# mcu.net
KiCad netlist of a schematic drawn in Altium Designer
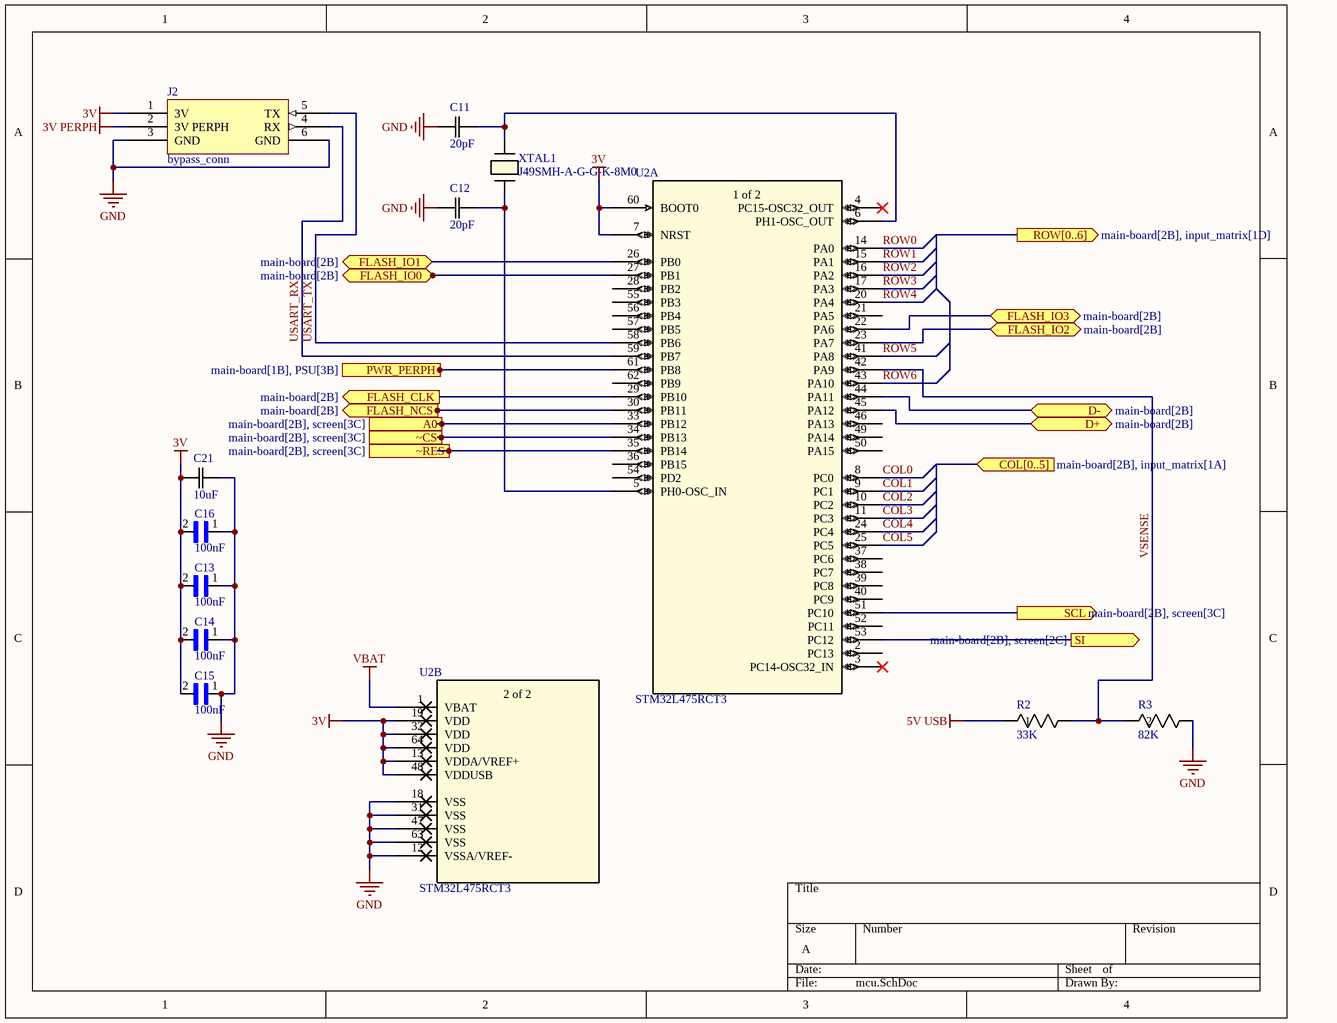
[diagram p0: mcu.SchDoc]

(export (version "E")
  (design (tool "Eeschema 10.0.6"))
  (components
    (comp (ref "C11")
      (value "20pF")
      (footprint "CAP_CL10_SAM")
      (description "CL10C200JB8NNNC")
      (libsource (lib "CL10C200JB8NNNC") (part "CL10C200JB8NNNC"))
    )
    (comp (ref "C12")
      (value "20pF")
      (footprint "CAP_CL10_SAM")
      (description "CL10C200JB8NNNC")
      (libsource (lib "CL10C200JB8NNNC") (part "CL10C200JB8NNNC"))
    )
    (comp (ref "C13")
      (value "100nF")
      (footprint "CAPC1005X55N")
      (description "0.1ÂµF Â±10% 10V Ceramic Capacitor X7R 0402 _1005 Metric_")
      (fields (field (name "MP") "CL05B104KP5NNNC") (field (name "MF") "Samsung Electro-Mechanics"))
      (libsource (lib "CL05B104KP5NNNC") (part "CL05B104KP5NNNC"))
    )
    (comp (ref "C14")
      (value "100nF")
      (footprint "CAPC1005X55N")
      (description "0.1ÂµF Â±10% 10V Ceramic Capacitor X7R 0402 _1005 Metric_")
      (fields (field (name "MP") "CL05B104KP5NNNC") (field (name "MF") "Samsung Electro-Mechanics"))
      (libsource (lib "CL05B104KP5NNNC") (part "CL05B104KP5NNNC"))
    )
    (comp (ref "C15")
      (value "100nF")
      (footprint "CAPC1005X55N")
      (description "0.1ÂµF Â±10% 10V Ceramic Capacitor X7R 0402 _1005 Metric_")
      (fields (field (name "MP") "CL05B104KP5NNNC") (field (name "MF") "Samsung Electro-Mechanics"))
      (libsource (lib "CL05B104KP5NNNC") (part "CL05B104KP5NNNC"))
    )
    (comp (ref "C16")
      (value "100nF")
      (footprint "CAPC1005X55N")
      (description "0.1ÂµF Â±10% 10V Ceramic Capacitor X7R 0402 _1005 Metric_")
      (fields (field (name "MP") "CL05B104KP5NNNC") (field (name "MF") "Samsung Electro-Mechanics"))
      (libsource (lib "CL05B104KP5NNNC") (part "CL05B104KP5NNNC"))
    )
    (comp (ref "C21")
      (value "10uF")
      (footprint "CAP_CL10_SAM")
      (description "CL10A106KQ8NNNL")
      (libsource (lib "CL10A106KQ8NNNL") (part "CL10A106KQ8NNNL"))
    )
    (comp (ref "J2")
      (value "bypass_conn")
      (footprint "bypass_conn")
      (description "Bypass connector for power supply and backup chip programming")
      (libsource (lib "bypass_conn") (part "bypass_conn"))
    )
    (comp (ref "R2")
      (value "33K")
      (footprint "STA_RMCF0603_STP")
      (description "RMCF0603FT33K0")
      (libsource (lib "RMCF0603FT33K0") (part "RMCF0603FT33K0"))
    )
    (comp (ref "R3")
      (value "82K")
      (footprint "RC0603N_YAG")
      (description "RC0603FR-0782KL")
      (libsource (lib "RC0603FR-0782KL") (part "RC0603FR-0782KL"))
    )
    (comp (ref "U2")
      (value "STM32L475RCT3")
      (footprint "LQFP64-10x10mm")
      (description "No Description Available")
      (libsource (lib "STM32L475RCT3") (part "STM32L475RCT3"))
    )
    (comp (ref "XTAL1")
      (value "J49SMH-A-G-G-K-8M0")
      (footprint "XTAL_J49SMH-A-G-G-K-8M0_JAU")
      (description "No Description Available")
      (libsource (lib "J49SMH-A-G-G-K-8M0") (part "J49SMH-A-G-G-K-8M0"))
    )
  )
  (nets
    (net (code "1") (name "/A0") (class "Default")
      (node (ref "U2") (pin "33") (pinfunction "PB12_33") (pintype "bidirectional"))
    )
    (net (code "2") (name "/COL0") (class "Default")
      (node (ref "U2") (pin "8") (pinfunction "PC0_8") (pintype "bidirectional"))
    )
    (net (code "3") (name "/COL1") (class "Default")
      (node (ref "U2") (pin "9") (pinfunction "PC1_9") (pintype "bidirectional"))
    )
    (net (code "4") (name "/COL2") (class "Default")
      (node (ref "U2") (pin "10") (pinfunction "PC2_10") (pintype "bidirectional"))
    )
    (net (code "5") (name "/COL3") (class "Default")
      (node (ref "U2") (pin "11") (pinfunction "PC3_11") (pintype "bidirectional"))
    )
    (net (code "6") (name "/COL4") (class "Default")
      (node (ref "U2") (pin "24") (pinfunction "PC4_24") (pintype "bidirectional"))
    )
    (net (code "7") (name "/COL5") (class "Default")
      (node (ref "U2") (pin "25") (pinfunction "PC5_25") (pintype "bidirectional"))
    )
    (net (code "9") (name "/D+") (class "Default")
      (node (ref "U2") (pin "45") (pinfunction "PA12_45") (pintype "bidirectional"))
    )
    (net (code "10") (name "/D-") (class "Default")
      (node (ref "U2") (pin "44") (pinfunction "PA11_44") (pintype "bidirectional"))
    )
    (net (code "11") (name "/FLASH_CLK") (class "Default")
      (node (ref "U2") (pin "29") (pinfunction "PB10_29") (pintype "bidirectional"))
    )
    (net (code "12") (name "/FLASH_IO0") (class "Default")
      (node (ref "U2") (pin "27") (pinfunction "PB1_27") (pintype "bidirectional"))
    )
    (net (code "13") (name "/FLASH_IO1") (class "Default")
      (node (ref "U2") (pin "26") (pinfunction "PB0_26") (pintype "bidirectional"))
    )
    (net (code "14") (name "/FLASH_IO2") (class "Default")
      (node (ref "U2") (pin "23") (pinfunction "PA7_23") (pintype "bidirectional"))
    )
    (net (code "15") (name "/FLASH_IO3") (class "Default")
      (node (ref "U2") (pin "22") (pinfunction "PA6_22") (pintype "bidirectional"))
    )
    (net (code "16") (name "/FLASH_NCS") (class "Default")
      (node (ref "U2") (pin "30") (pinfunction "PB11_30") (pintype "bidirectional"))
    )
    (net (code "17") (name "/PWR_PERPH") (class "Default")
      (node (ref "U2") (pin "61") (pinfunction "PB8_61") (pintype "bidirectional"))
    )
    (net (code "18") (name "/ROW0") (class "Default")
      (node (ref "U2") (pin "14") (pinfunction "PA0_14") (pintype "bidirectional"))
    )
    (net (code "19") (name "/ROW1") (class "Default")
      (node (ref "U2") (pin "15") (pinfunction "PA1_15") (pintype "bidirectional"))
    )
    (net (code "20") (name "/ROW2") (class "Default")
      (node (ref "U2") (pin "16") (pinfunction "PA2_16") (pintype "bidirectional"))
    )
    (net (code "21") (name "/ROW3") (class "Default")
      (node (ref "U2") (pin "17") (pinfunction "PA3_17") (pintype "bidirectional"))
    )
    (net (code "22") (name "/ROW4") (class "Default")
      (node (ref "U2") (pin "20") (pinfunction "PA4_20") (pintype "bidirectional"))
    )
    (net (code "23") (name "/ROW5") (class "Default")
      (node (ref "U2") (pin "41") (pinfunction "PA8_41") (pintype "bidirectional"))
    )
    (net (code "24") (name "/ROW6") (class "Default")
      (node (ref "U2") (pin "43") (pinfunction "PA10_43") (pintype "bidirectional"))
    )
    (net (code "26") (name "/SCL") (class "Default")
      (node (ref "U2") (pin "51") (pinfunction "PC10_51") (pintype "bidirectional"))
    )
    (net (code "27") (name "/SI") (class "Default")
      (node (ref "U2") (pin "53") (pinfunction "PC12_53") (pintype "bidirectional"))
    )
    (net (code "28") (name "/USART_RX") (class "Default")
      (node (ref "J2") (pin "4") (pinfunction "RX_4") (pintype "output"))
      (node (ref "U2") (pin "59") (pinfunction "PB7_59") (pintype "bidirectional"))
    )
    (net (code "29") (name "/USART_TX") (class "Default")
      (node (ref "J2") (pin "5") (pinfunction "TX_5") (pintype "input"))
      (node (ref "U2") (pin "58") (pinfunction "PB6_58") (pintype "bidirectional"))
    )
    (net (code "30") (name "/VSENSE") (class "Default")
      (node (ref "R2") (pin "2") (pinfunction "2_2") (pintype "passive"))
      (node (ref "R3") (pin "2") (pinfunction "2_2") (pintype "passive"))
      (node (ref "U2") (pin "42") (pinfunction "PA9_42") (pintype "bidirectional"))
    )
    (net (code "31") (name "/~CS") (class "Default")
      (node (ref "U2") (pin "34") (pinfunction "PB13_34") (pintype "bidirectional"))
    )
    (net (code "32") (name "/~RES") (class "Default")
      (node (ref "U2") (pin "35") (pinfunction "PB14_35") (pintype "bidirectional"))
    )
    (net (code "33") (name "3V") (class "Default")
      (node (ref "C13") (pin "2") (pinfunction "2_2") (pintype "passive"))
      (node (ref "C14") (pin "2") (pinfunction "2_2") (pintype "passive"))
      (node (ref "C15") (pin "2") (pinfunction "2_2") (pintype "passive"))
      (node (ref "C16") (pin "2") (pinfunction "2_2") (pintype "passive"))
      (node (ref "C21") (pin "1") (pinfunction "1_1") (pintype "passive"))
      (node (ref "J2") (pin "1") (pinfunction "3V_1") (pintype "power_in"))
      (node (ref "U2") (pin "13") (pinfunction "VDDA/VREF+_13") (pintype "power_in"))
      (node (ref "U2") (pin "19") (pinfunction "VDD_19") (pintype "power_in"))
      (node (ref "U2") (pin "32") (pinfunction "VDD_32") (pintype "power_in"))
      (node (ref "U2") (pin "48") (pinfunction "VDDUSB_48") (pintype "power_in"))
      (node (ref "U2") (pin "60") (pinfunction "BOOT0_60") (pintype "input"))
      (node (ref "U2") (pin "64") (pinfunction "VDD_64") (pintype "power_in"))
      (node (ref "U2") (pin "7") (pinfunction "NRST_7") (pintype "bidirectional"))
    )
    (net (code "34") (name "3V PERPH") (class "Default")
      (node (ref "J2") (pin "2") (pinfunction "3V_PERPH_2") (pintype "power_in"))
    )
    (net (code "35") (name "5V USB") (class "Default")
      (node (ref "R2") (pin "1") (pinfunction "1_1") (pintype "passive"))
    )
    (net (code "36") (name "GND") (class "Default")
      (node (ref "C11") (pin "1") (pinfunction "1_1") (pintype "passive"))
      (node (ref "C12") (pin "1") (pinfunction "1_1") (pintype "passive"))
      (node (ref "C13") (pin "1") (pinfunction "1_1") (pintype "passive"))
      (node (ref "C14") (pin "1") (pinfunction "1_1") (pintype "passive"))
      (node (ref "C15") (pin "1") (pinfunction "1_1") (pintype "passive"))
      (node (ref "C16") (pin "1") (pinfunction "1_1") (pintype "passive"))
      (node (ref "C21") (pin "2") (pinfunction "2_2") (pintype "passive"))
      (node (ref "J2") (pin "3") (pinfunction "GND_3") (pintype "power_in"))
      (node (ref "J2") (pin "6") (pinfunction "GND_6") (pintype "power_in"))
      (node (ref "R3") (pin "1") (pinfunction "1_1") (pintype "passive"))
      (node (ref "U2") (pin "12") (pinfunction "VSSA/VREF-_12") (pintype "power_in"))
      (node (ref "U2") (pin "18") (pinfunction "VSS_18") (pintype "power_in"))
      (node (ref "U2") (pin "31") (pinfunction "VSS_31") (pintype "power_in"))
      (node (ref "U2") (pin "47") (pinfunction "VSS_47") (pintype "power_in"))
      (node (ref "U2") (pin "63") (pinfunction "VSS_63") (pintype "power_in"))
    )
    (net (code "37") (name "Net-(U2A-PH0-OSC_IN)") (class "Default")
      (node (ref "C12") (pin "2") (pinfunction "2_2") (pintype "passive"))
      (node (ref "U2") (pin "5") (pinfunction "PH0-OSC_IN_5") (pintype "bidirectional"))
      (node (ref "XTAL1") (pin "1") (pinfunction "1_1") (pintype "passive"))
    )
    (net (code "38") (name "Net-(U2A-PH1-OSC_OUT)") (class "Default")
      (node (ref "C11") (pin "2") (pinfunction "2_2") (pintype "passive"))
      (node (ref "U2") (pin "6") (pinfunction "PH1-OSC_OUT_6") (pintype "bidirectional"))
      (node (ref "XTAL1") (pin "2") (pinfunction "2_2") (pintype "passive"))
    )
    (net (code "39") (name "VBAT") (class "Default")
      (node (ref "U2") (pin "1") (pinfunction "VBAT_1") (pintype "power_in"))
    )
    (net (code "40") (name "unconnected-(U2A-PA5-Pad21)") (class "Default")
      (node (ref "U2") (pin "21") (pinfunction "PA5_21") (pintype "bidirectional"))
    )
    (net (code "41") (name "unconnected-(U2A-PA13-Pad46)") (class "Default")
      (node (ref "U2") (pin "46") (pinfunction "PA13_46") (pintype "bidirectional"))
    )
    (net (code "42") (name "unconnected-(U2A-PA14-Pad49)") (class "Default")
      (node (ref "U2") (pin "49") (pinfunction "PA14_49") (pintype "bidirectional"))
    )
    (net (code "43") (name "unconnected-(U2A-PA15-Pad50)") (class "Default")
      (node (ref "U2") (pin "50") (pinfunction "PA15_50") (pintype "bidirectional"))
    )
    (net (code "44") (name "unconnected-(U2A-PB2-Pad28)") (class "Default")
      (node (ref "U2") (pin "28") (pinfunction "PB2_28") (pintype "bidirectional"))
    )
    (net (code "45") (name "unconnected-(U2A-PB3-Pad55)") (class "Default")
      (node (ref "U2") (pin "55") (pinfunction "PB3_55") (pintype "bidirectional"))
    )
    (net (code "46") (name "unconnected-(U2A-PB4-Pad56)") (class "Default")
      (node (ref "U2") (pin "56") (pinfunction "PB4_56") (pintype "bidirectional"))
    )
    (net (code "47") (name "unconnected-(U2A-PB5-Pad57)") (class "Default")
      (node (ref "U2") (pin "57") (pinfunction "PB5_57") (pintype "bidirectional"))
    )
    (net (code "48") (name "unconnected-(U2A-PB9-Pad62)") (class "Default")
      (node (ref "U2") (pin "62") (pinfunction "PB9_62") (pintype "bidirectional"))
    )
    (net (code "49") (name "unconnected-(U2A-PB15-Pad36)") (class "Default")
      (node (ref "U2") (pin "36") (pinfunction "PB15_36") (pintype "bidirectional"))
    )
    (net (code "50") (name "unconnected-(U2A-PC6-Pad37)") (class "Default")
      (node (ref "U2") (pin "37") (pinfunction "PC6_37") (pintype "bidirectional"))
    )
    (net (code "51") (name "unconnected-(U2A-PC7-Pad38)") (class "Default")
      (node (ref "U2") (pin "38") (pinfunction "PC7_38") (pintype "bidirectional"))
    )
    (net (code "52") (name "unconnected-(U2A-PC8-Pad39)") (class "Default")
      (node (ref "U2") (pin "39") (pinfunction "PC8_39") (pintype "bidirectional"))
    )
    (net (code "53") (name "unconnected-(U2A-PC9-Pad40)") (class "Default")
      (node (ref "U2") (pin "40") (pinfunction "PC9_40") (pintype "bidirectional"))
    )
    (net (code "54") (name "unconnected-(U2A-PC11-Pad52)") (class "Default")
      (node (ref "U2") (pin "52") (pinfunction "PC11_52") (pintype "bidirectional"))
    )
    (net (code "55") (name "unconnected-(U2A-PC13-Pad2)") (class "Default")
      (node (ref "U2") (pin "2") (pinfunction "PC13_2") (pintype "bidirectional"))
    )
    (net (code "56") (name "unconnected-(U2A-PC14-OSC32_IN-Pad3)") (class "Default")
      (node (ref "U2") (pin "3") (pinfunction "PC14-OSC32_IN_3") (pintype "bidirectional+no_connect"))
    )
    (net (code "57") (name "unconnected-(U2A-PC15-OSC32_OUT-Pad4)") (class "Default")
      (node (ref "U2") (pin "4") (pinfunction "PC15-OSC32_OUT_4") (pintype "bidirectional+no_connect"))
    )
    (net (code "58") (name "unconnected-(U2A-PD2-Pad54)") (class "Default")
      (node (ref "U2") (pin "54") (pinfunction "PD2_54") (pintype "bidirectional"))
    )
  )
)
